# DROID.net
KiCad netlist of a schematic drawn in EAGLE
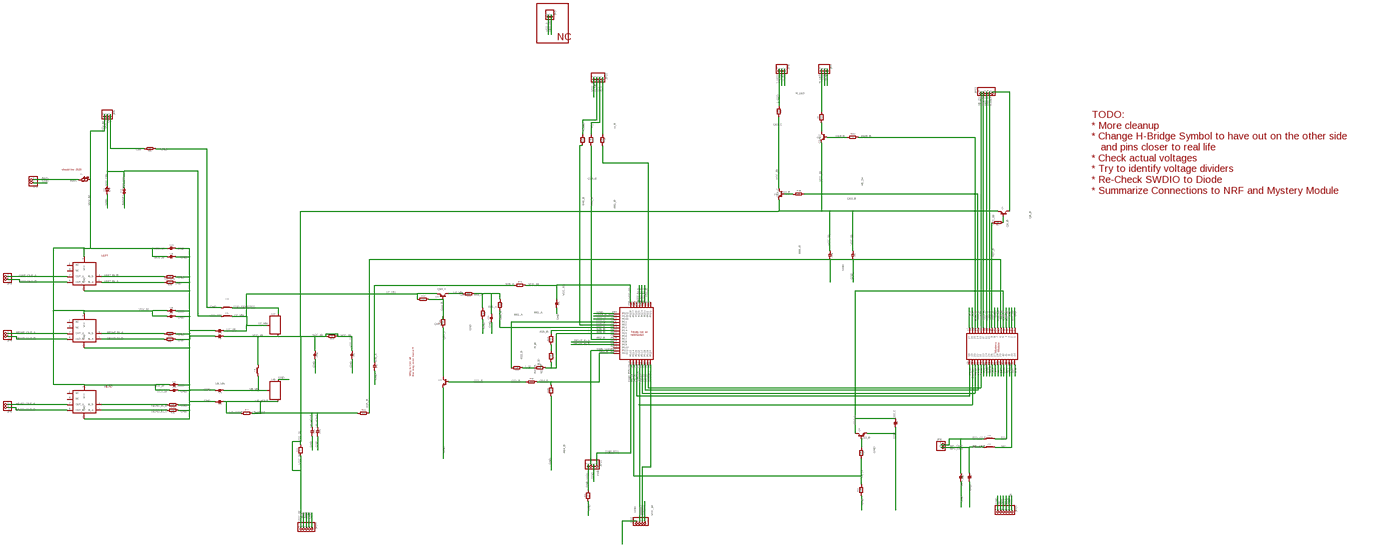
[diagram p0: schematic, sheet 1, overview]
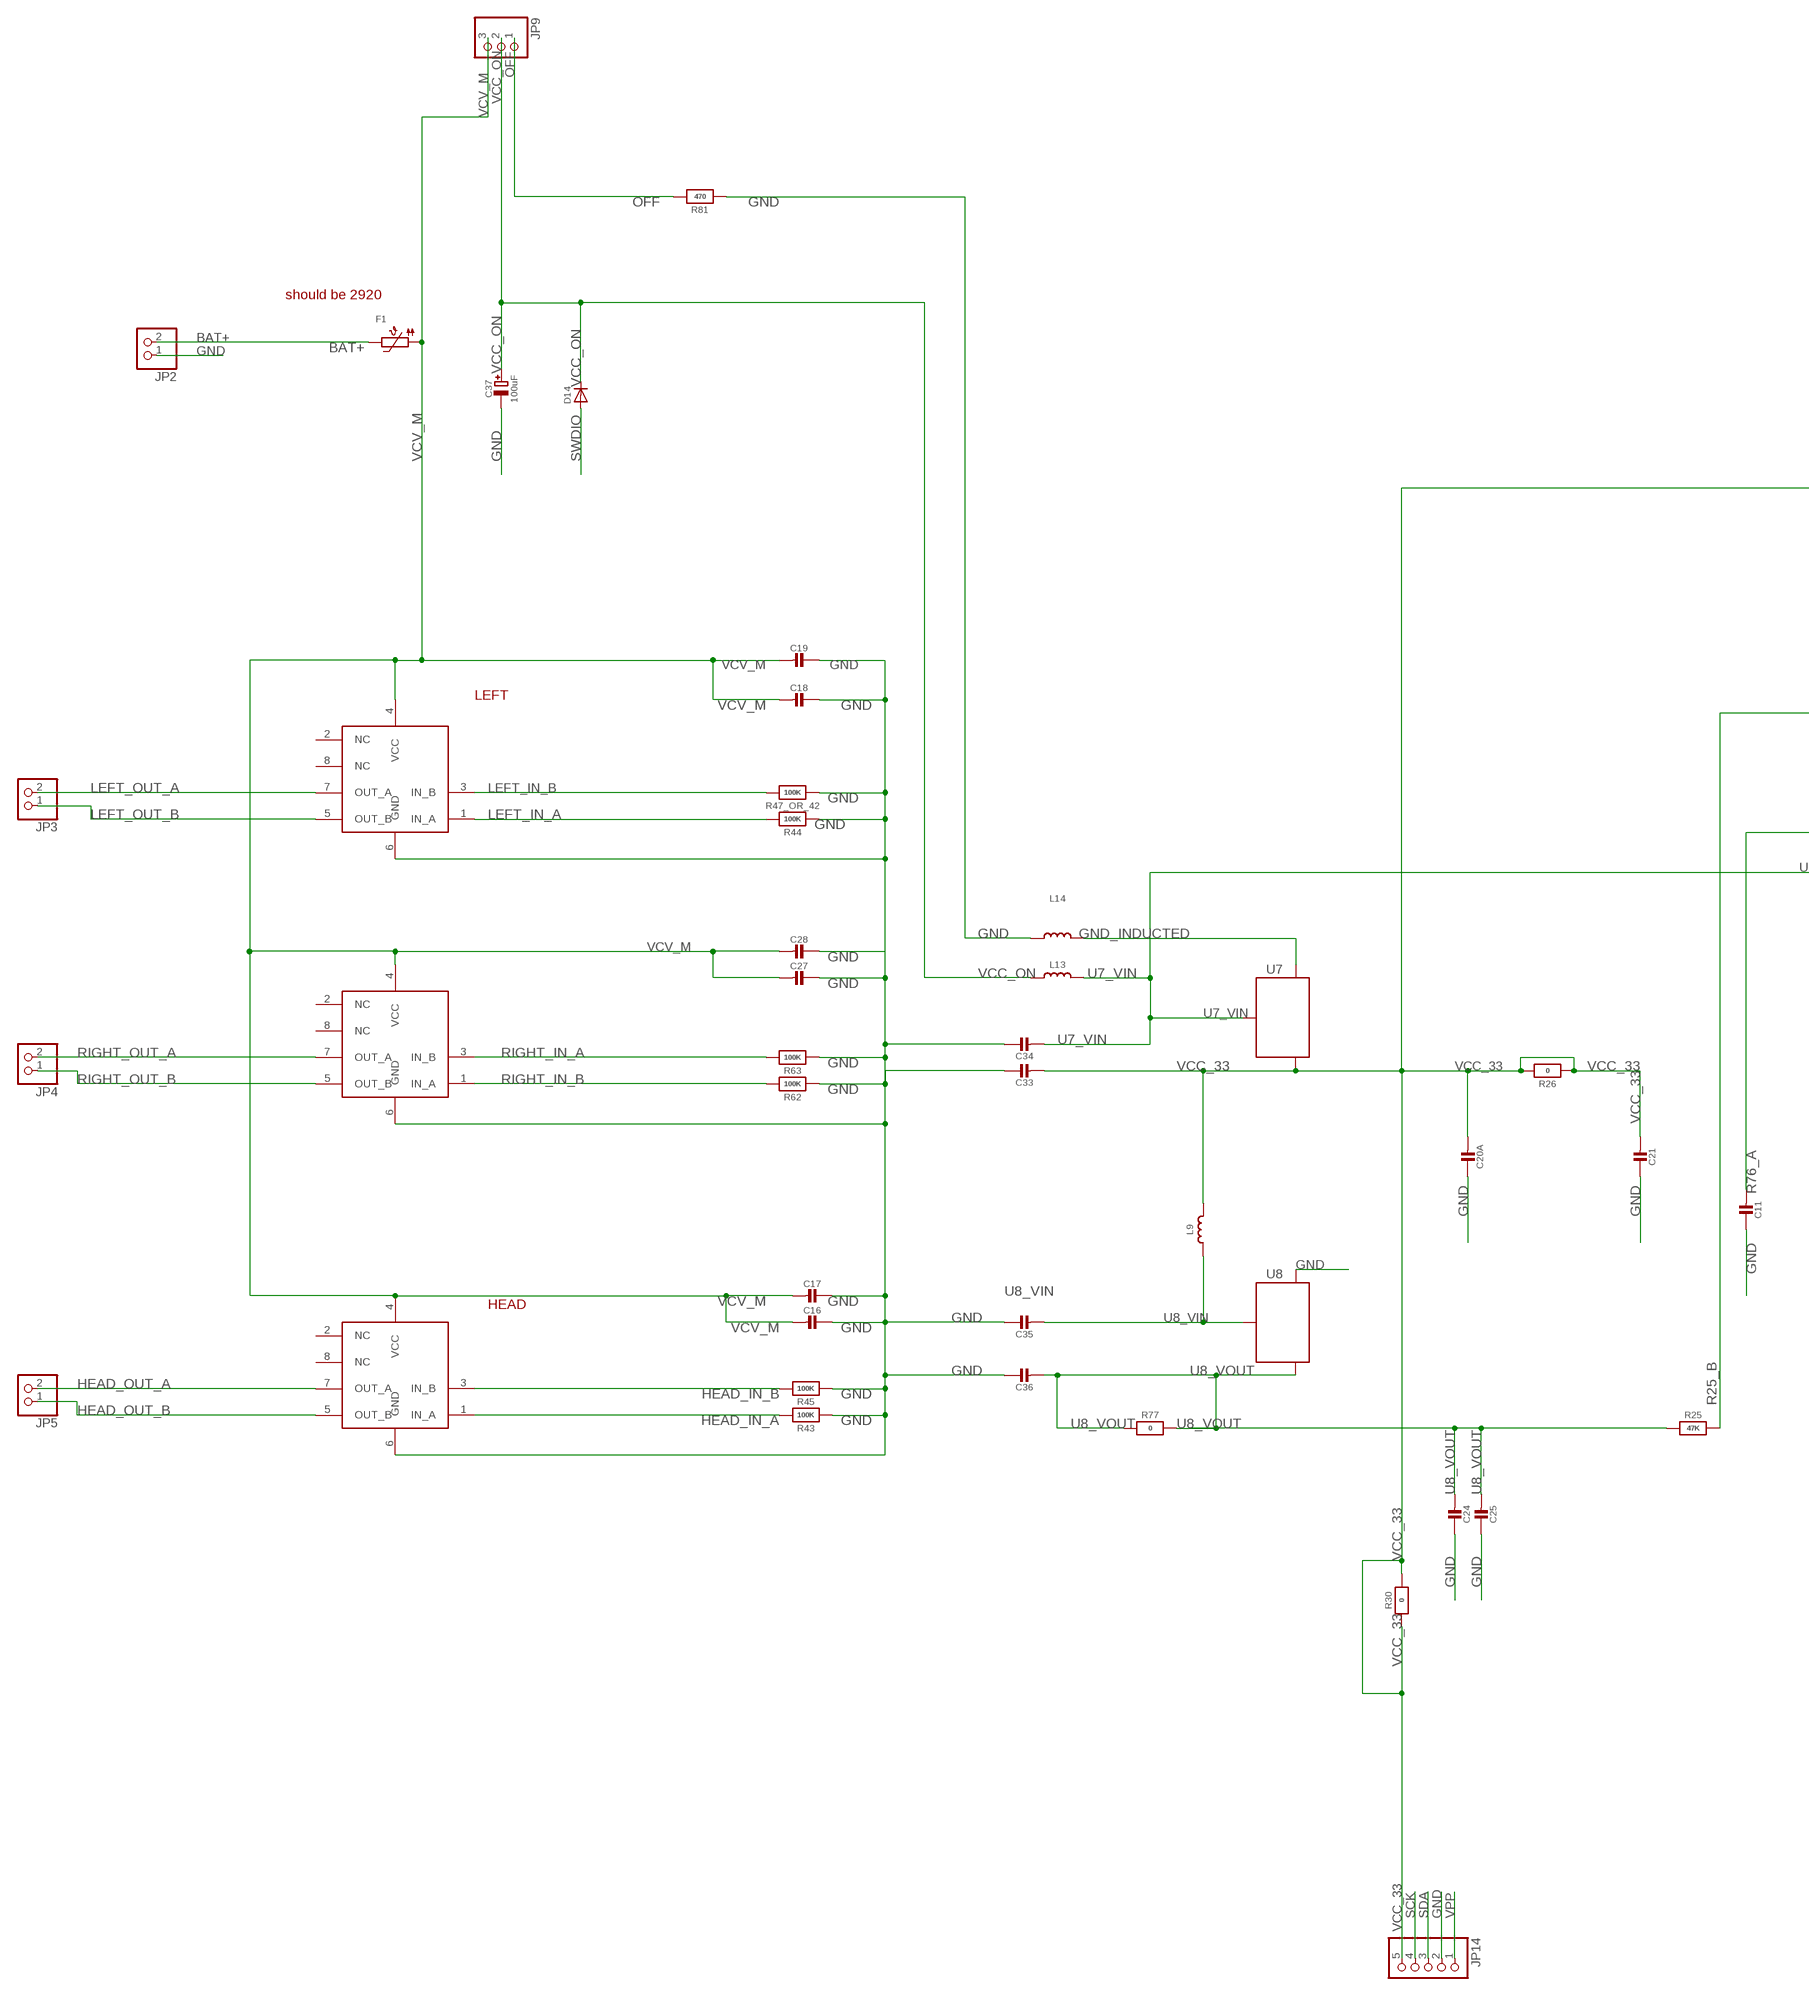
[diagram p1: schematic, sheet 1, part 1 of 5]
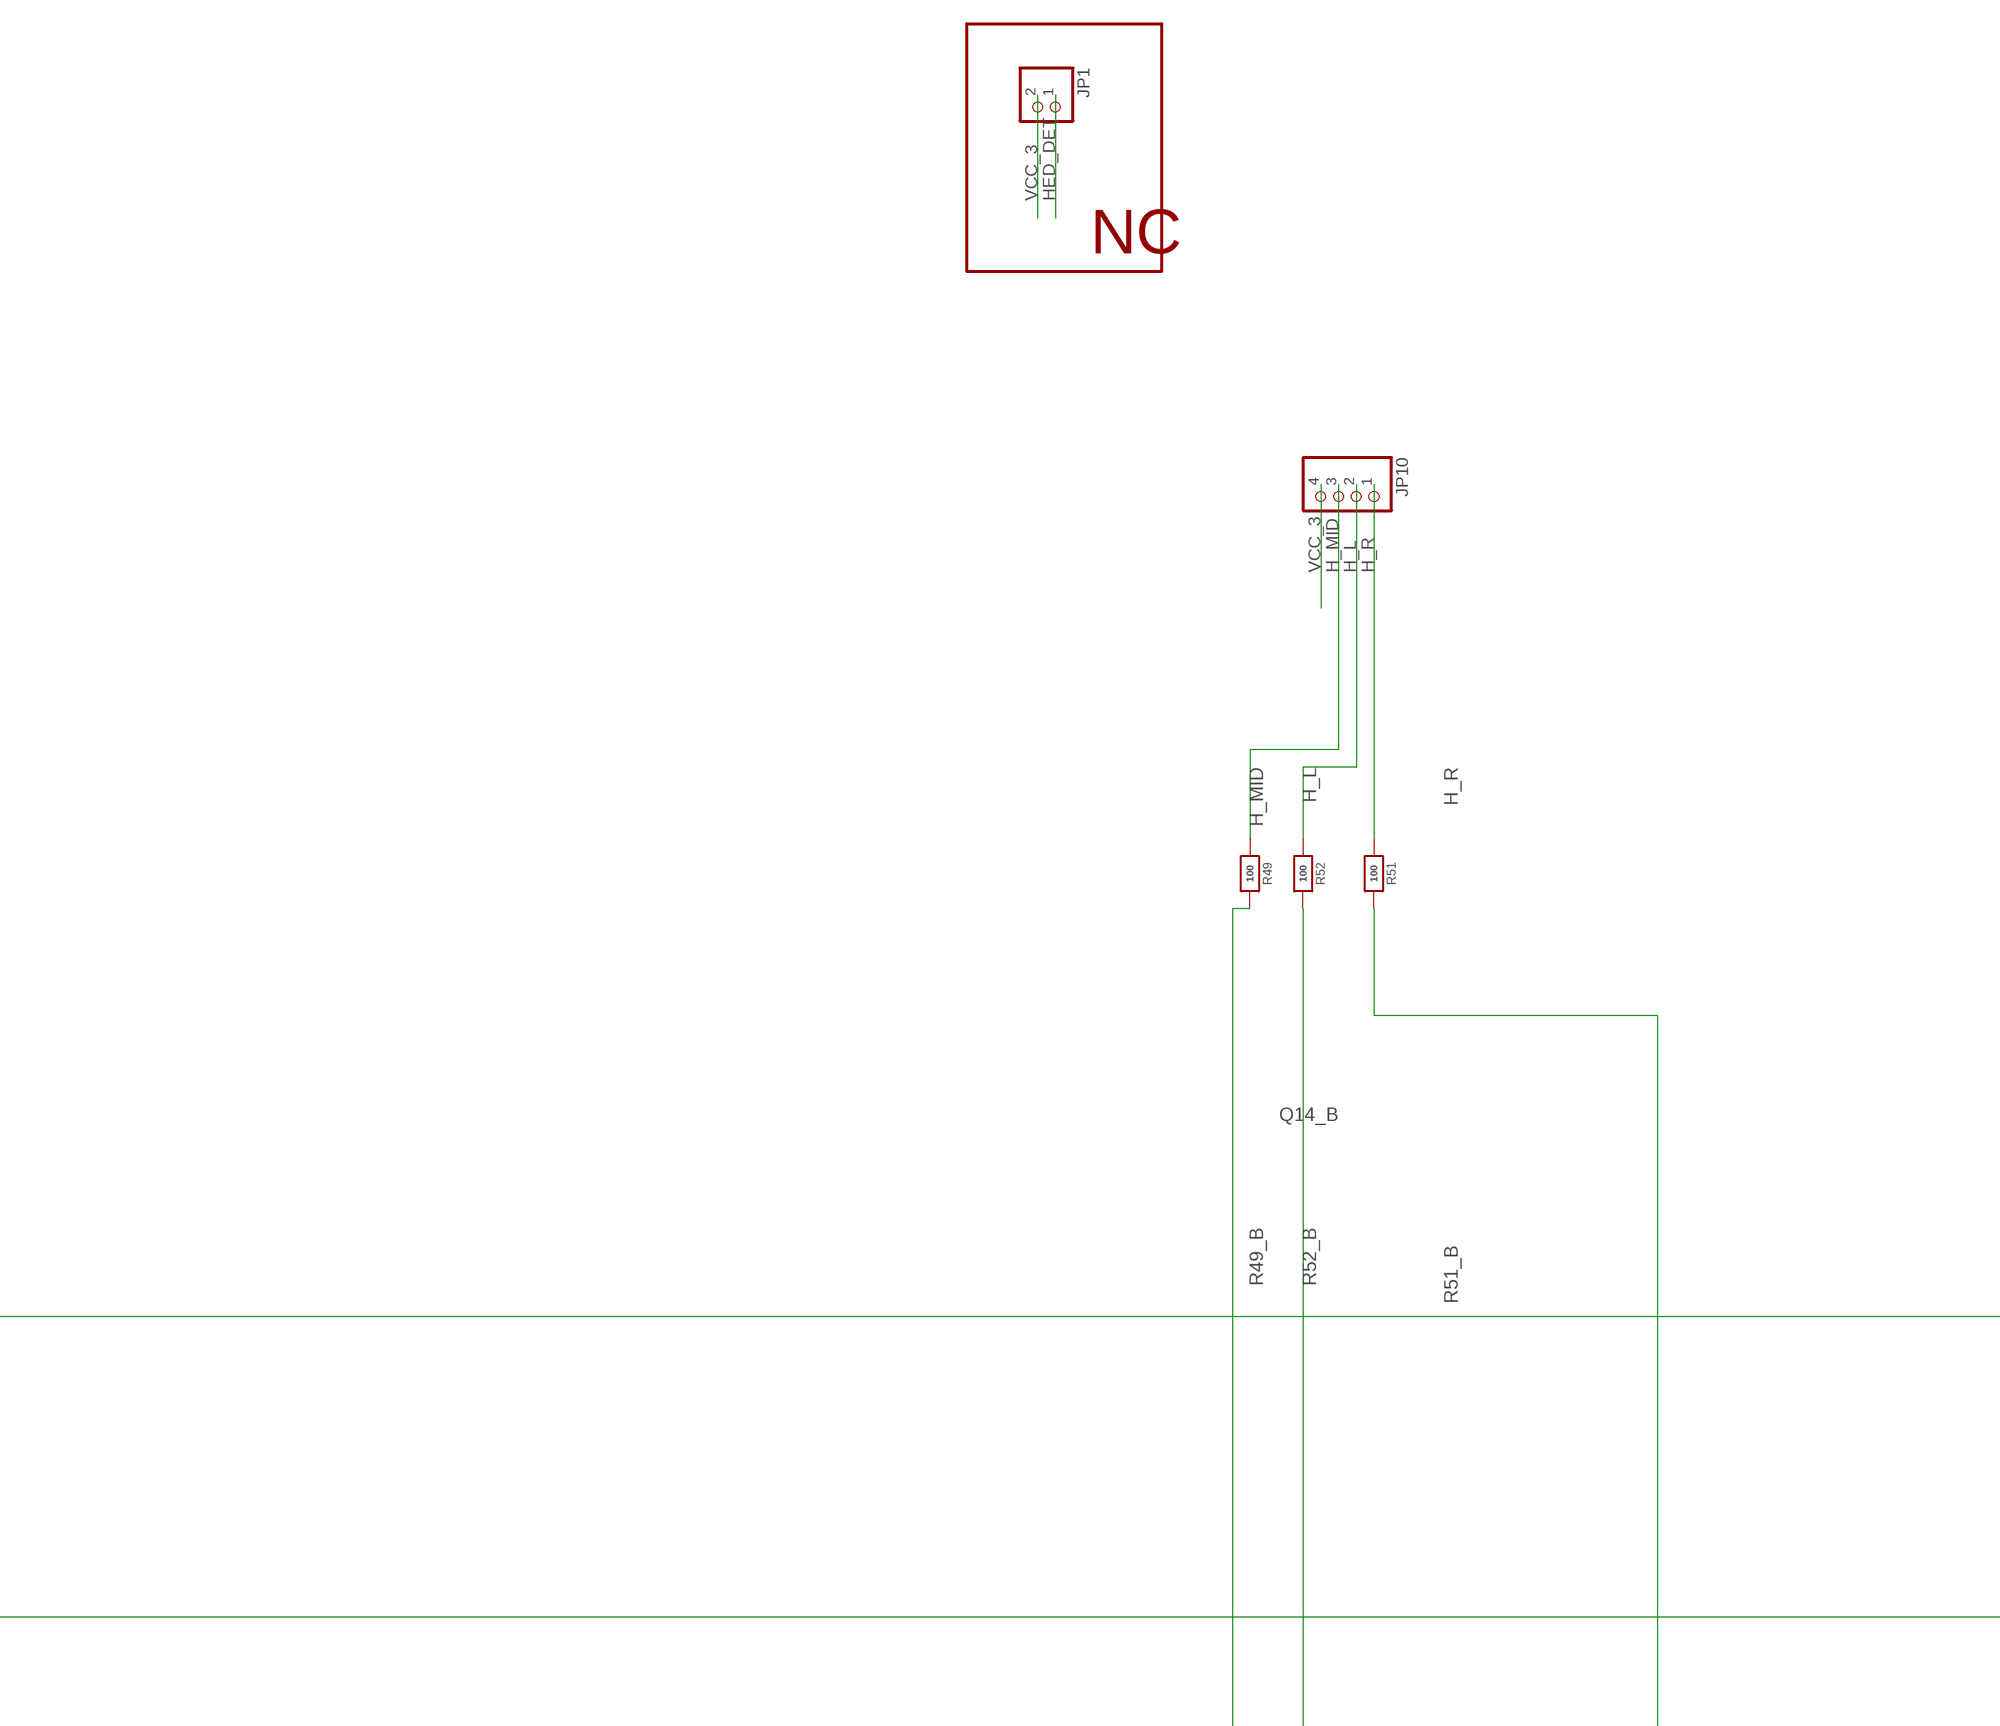
[diagram p2: schematic, sheet 1, part 2 of 5]
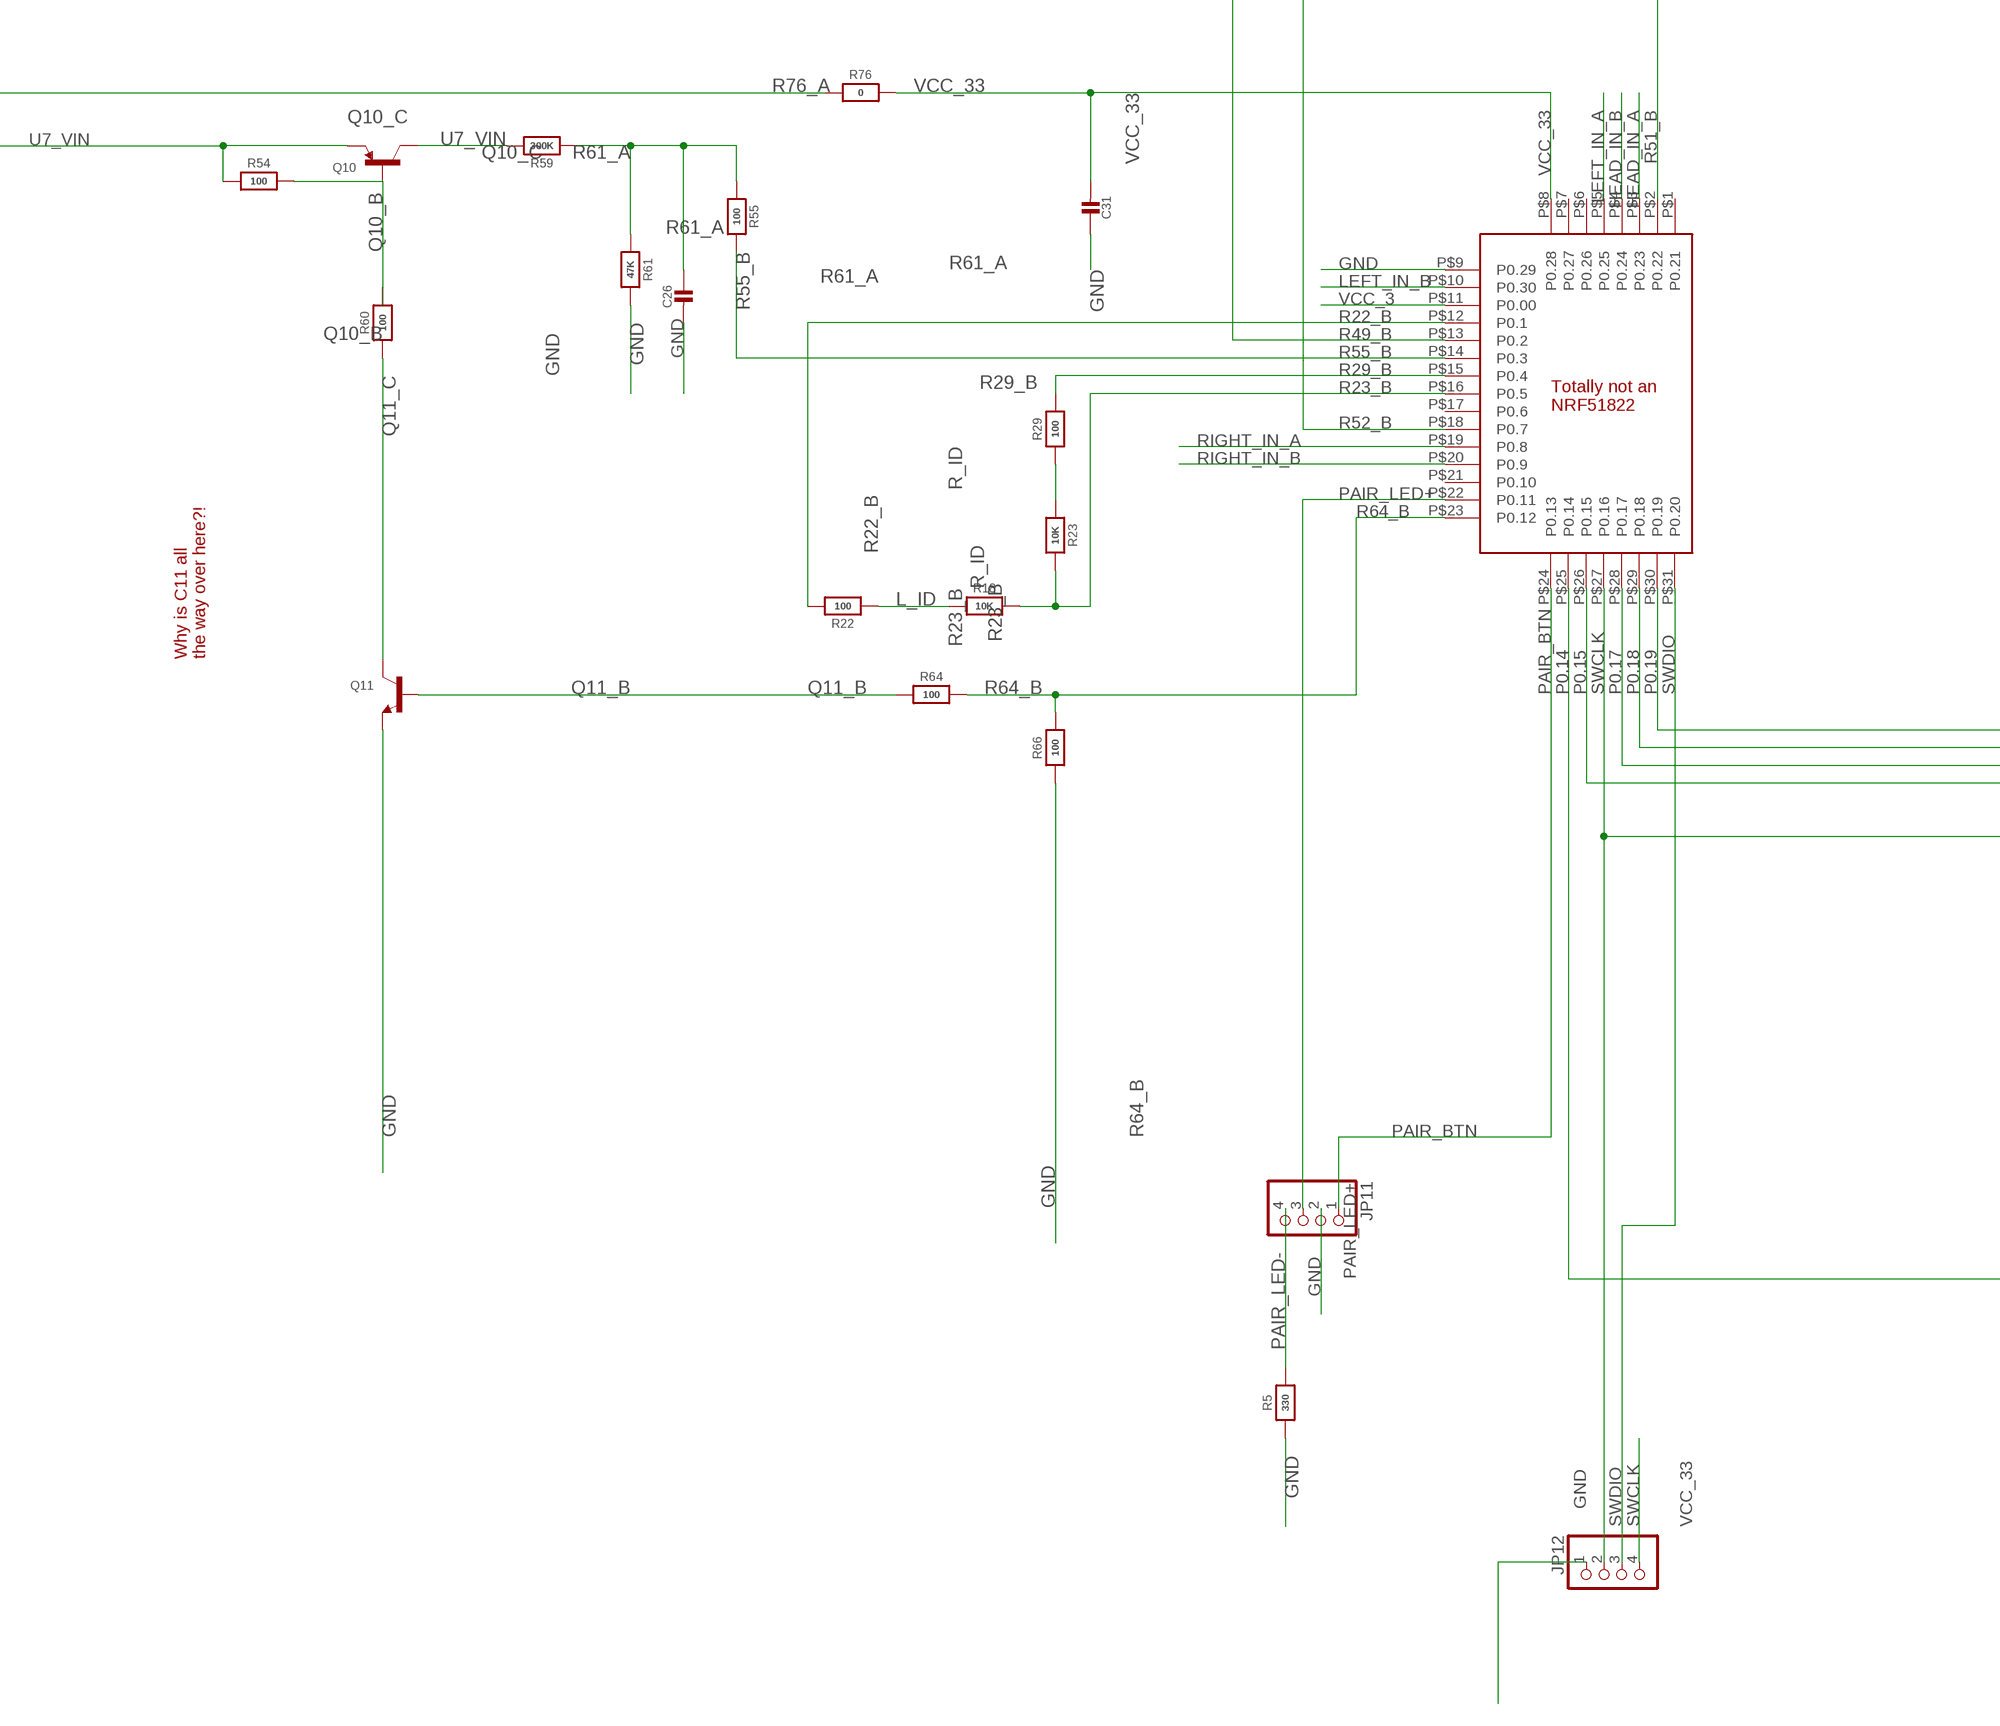
[diagram p3: schematic, sheet 1, part 3 of 5]
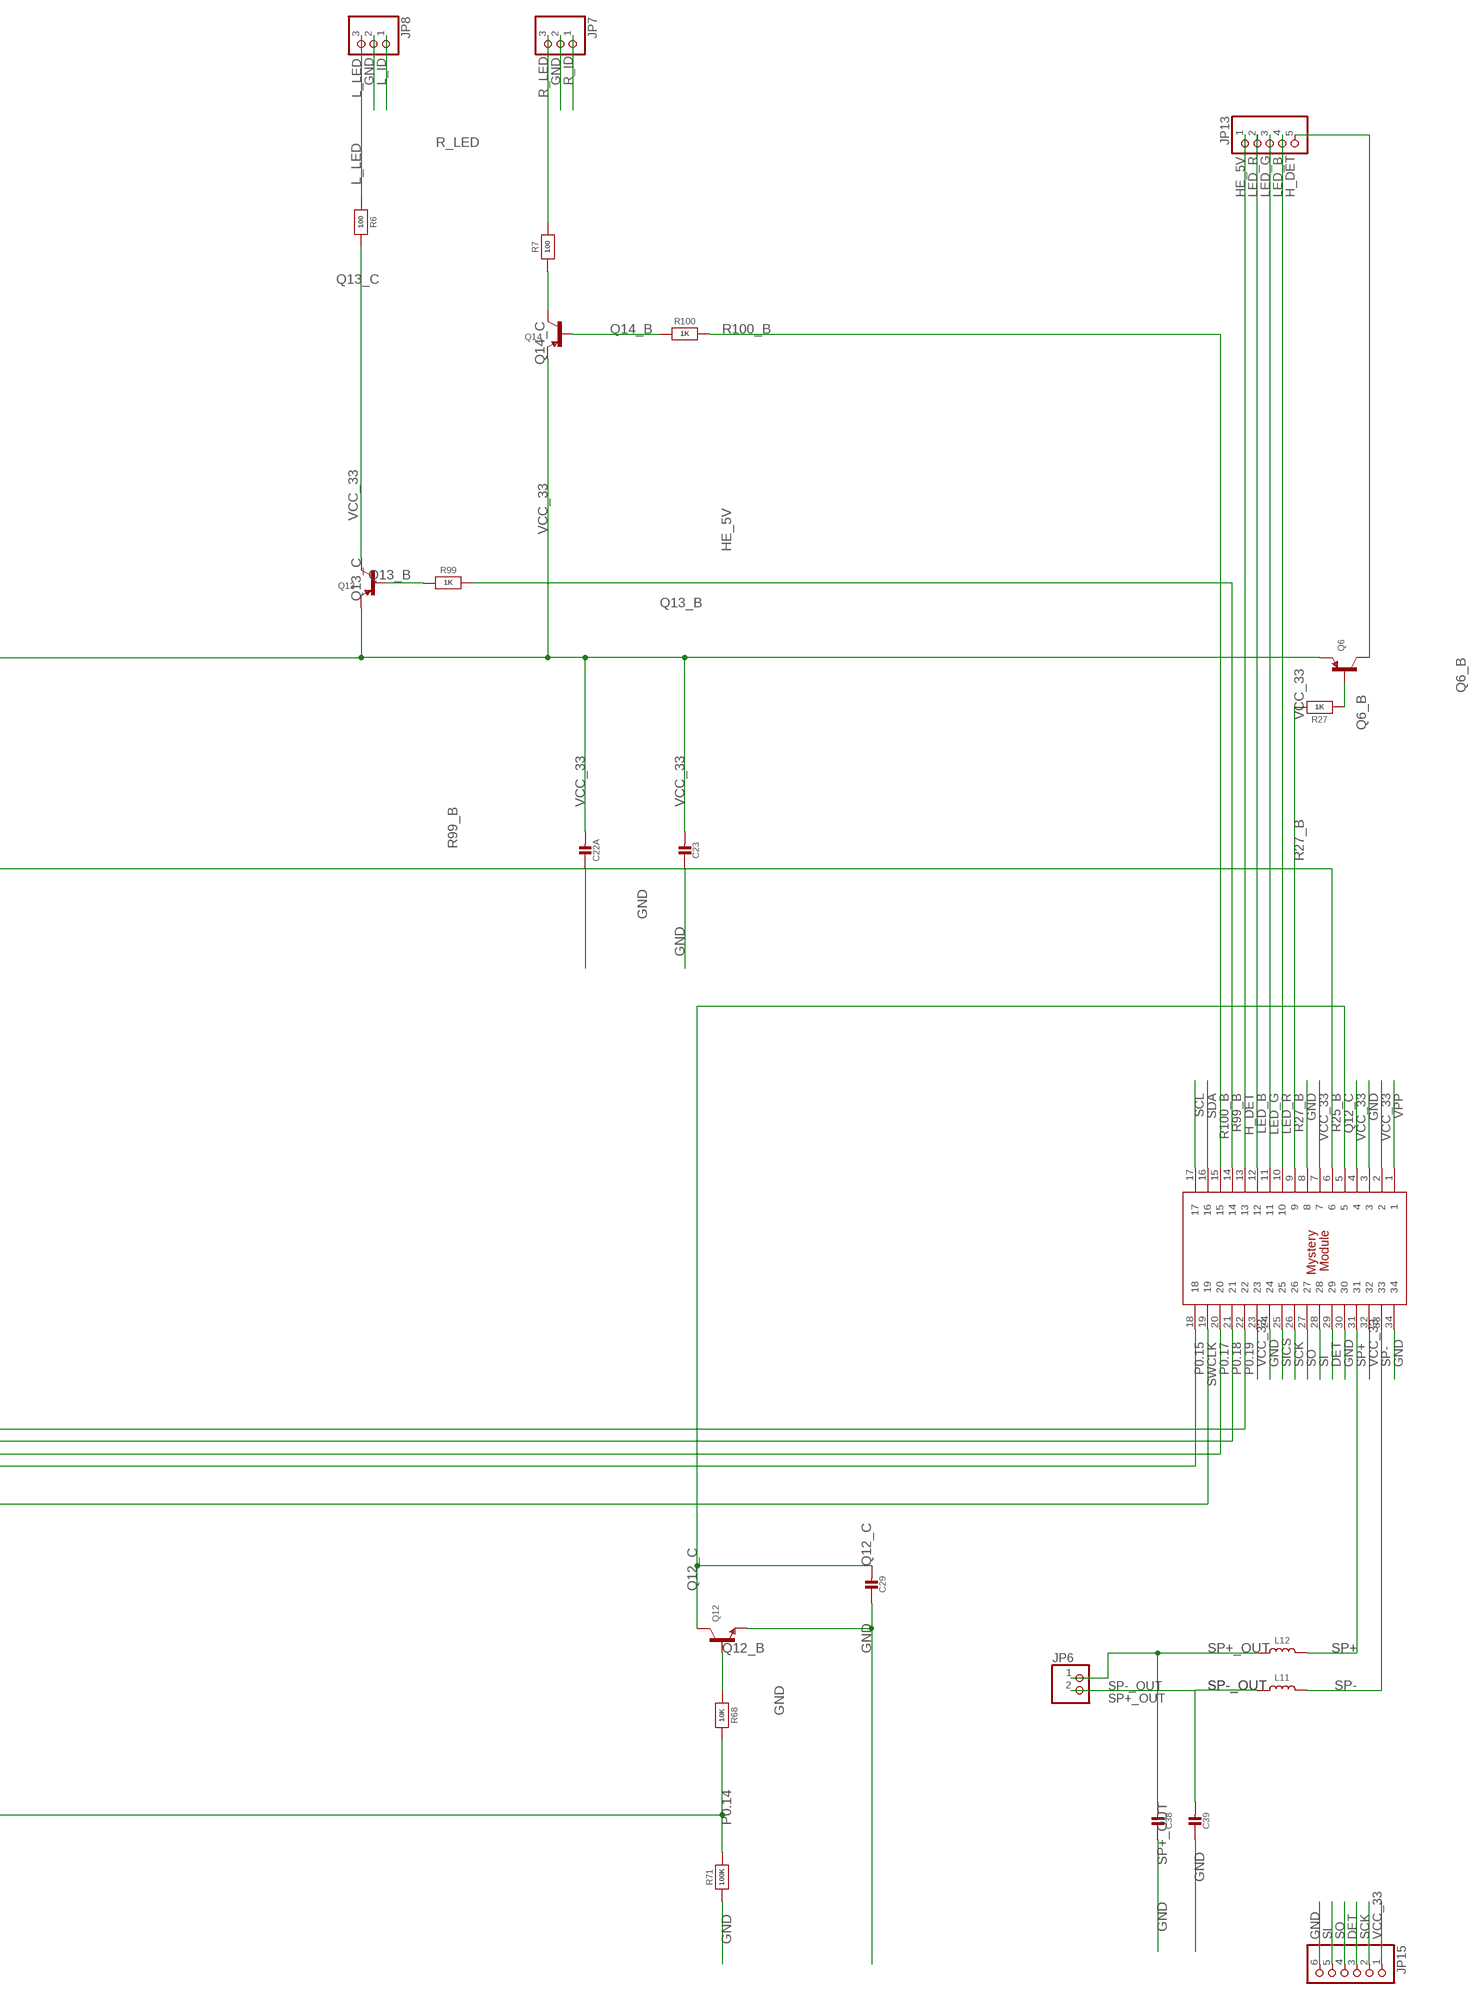
[diagram p4: schematic, sheet 1, part 4 of 5]
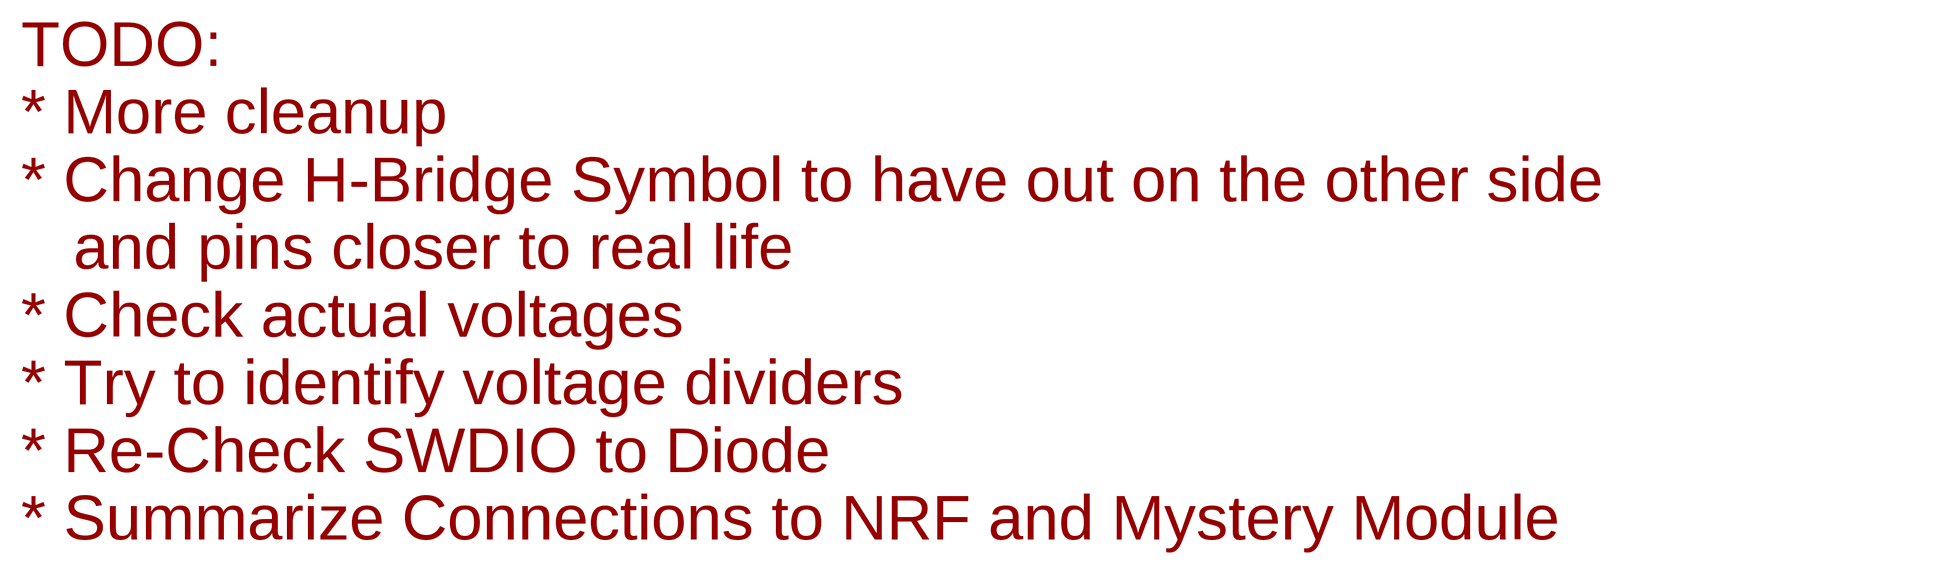
[diagram p5: schematic, sheet 1, part 5 of 5]

(export (version "E")
  (design (tool "Eeschema 10.0.6"))
  (components
    (comp (ref "C11")
      (value "CAP_CERAMIC0603_NO")
      (footprint "eagle-import:0603-NO")
      (libsource (lib "eagle-import") (part "CAP_CERAMIC0603_NO"))
    )
    (comp (ref "C16")
      (value "CAP_CERAMIC0603_NO")
      (footprint "eagle-import:0603-NO")
      (libsource (lib "eagle-import") (part "CAP_CERAMIC0603_NO"))
    )
    (comp (ref "C17")
      (value "CAP_CERAMIC_0805MP")
      (footprint "eagle-import:_0805MP")
      (libsource (lib "eagle-import") (part "CAP_CERAMIC_0805MP"))
    )
    (comp (ref "C18")
      (value "CAP_CERAMIC0603_NO")
      (footprint "eagle-import:0603-NO")
      (libsource (lib "eagle-import") (part "CAP_CERAMIC0603_NO"))
    )
    (comp (ref "C19")
      (value "CAP_CERAMIC_0805MP")
      (footprint "eagle-import:_0805MP")
      (libsource (lib "eagle-import") (part "CAP_CERAMIC_0805MP"))
    )
    (comp (ref "C20A")
      (value "CAP_CERAMIC_0805MP")
      (footprint "eagle-import:_0805MP")
      (libsource (lib "eagle-import") (part "CAP_CERAMIC_0805MP"))
    )
    (comp (ref "C21")
      (value "CAP_CERAMIC0603_NO")
      (footprint "eagle-import:0603-NO")
      (libsource (lib "eagle-import") (part "CAP_CERAMIC0603_NO"))
    )
    (comp (ref "C22A")
      (value "CAP_CERAMIC_0805MP")
      (footprint "eagle-import:_0805MP")
      (libsource (lib "eagle-import") (part "CAP_CERAMIC_0805MP"))
    )
    (comp (ref "C23")
      (value "CAP_CERAMIC0603_NO")
      (footprint "eagle-import:0603-NO")
      (libsource (lib "eagle-import") (part "CAP_CERAMIC0603_NO"))
    )
    (comp (ref "C24")
      (value "CAP_CERAMIC0603_NO")
      (footprint "eagle-import:0603-NO")
      (libsource (lib "eagle-import") (part "CAP_CERAMIC0603_NO"))
    )
    (comp (ref "C25")
      (value "CAP_CERAMIC0603_NO")
      (footprint "eagle-import:0603-NO")
      (libsource (lib "eagle-import") (part "CAP_CERAMIC0603_NO"))
    )
    (comp (ref "C26")
      (value "CAP_CERAMIC0603_NO")
      (footprint "eagle-import:0603-NO")
      (libsource (lib "eagle-import") (part "CAP_CERAMIC0603_NO"))
    )
    (comp (ref "C27")
      (value "CAP_CERAMIC0603_NO")
      (footprint "eagle-import:0603-NO")
      (libsource (lib "eagle-import") (part "CAP_CERAMIC0603_NO"))
    )
    (comp (ref "C28")
      (value "CAP_CERAMIC_0805MP")
      (footprint "eagle-import:_0805MP")
      (libsource (lib "eagle-import") (part "CAP_CERAMIC_0805MP"))
    )
    (comp (ref "C29")
      (value "CAP_CERAMIC0603_NO")
      (footprint "eagle-import:0603-NO")
      (libsource (lib "eagle-import") (part "CAP_CERAMIC0603_NO"))
    )
    (comp (ref "C31")
      (value "CAP_CERAMIC0603_NO")
      (footprint "eagle-import:0603-NO")
      (libsource (lib "eagle-import") (part "CAP_CERAMIC0603_NO"))
    )
    (comp (ref "C33")
      (value "CAP_CERAMIC0603_NO")
      (footprint "eagle-import:0603-NO")
      (libsource (lib "eagle-import") (part "CAP_CERAMIC0603_NO"))
    )
    (comp (ref "C34")
      (value "CAP_CERAMIC0603_NO")
      (footprint "eagle-import:0603-NO")
      (libsource (lib "eagle-import") (part "CAP_CERAMIC0603_NO"))
    )
    (comp (ref "C35")
      (value "CAP_CERAMIC0603_NO")
      (footprint "eagle-import:0603-NO")
      (libsource (lib "eagle-import") (part "CAP_CERAMIC0603_NO"))
    )
    (comp (ref "C36")
      (value "CAP_CERAMIC0603_NO")
      (footprint "eagle-import:0603-NO")
      (libsource (lib "eagle-import") (part "CAP_CERAMIC0603_NO"))
    )
    (comp (ref "C37")
      (value "100uF")
      (footprint "eagle-import:PANASONIC_D")
      (libsource (lib "eagle-import") (part "CAP_ELECTROLYTICPANASONIC_D"))
    )
    (comp (ref "C38")
      (value "CAP_CERAMIC0603_NO")
      (footprint "eagle-import:0603-NO")
      (libsource (lib "eagle-import") (part "CAP_CERAMIC0603_NO"))
    )
    (comp (ref "C39")
      (value "CAP_CERAMIC0603_NO")
      (footprint "eagle-import:0603-NO")
      (libsource (lib "eagle-import") (part "CAP_CERAMIC0603_NO"))
    )
    (comp (ref "D14")
      (value "DIODESOD-323")
      (footprint "eagle-import:SOD-323")
      (libsource (lib "eagle-import") (part "DIODESOD-323"))
    )
    (comp (ref "F1")
      (value "PTC1812")
      (footprint "eagle-import:PTC1812")
      (libsource (lib "eagle-import") (part "PTC1812"))
    )
    (comp (ref "JP1")
      (value "HEADER-1X2ROUND")
      (footprint "eagle-import:1X02_ROUND")
      (libsource (lib "eagle-import") (part "HEADER-1X2ROUND"))
    )
    (comp (ref "JP2")
      (value "HEADER-1X2ROUND")
      (footprint "eagle-import:1X02_ROUND")
      (libsource (lib "eagle-import") (part "HEADER-1X2ROUND"))
    )
    (comp (ref "JP3")
      (value "HEADER-1X2ROUND")
      (footprint "eagle-import:1X02_ROUND")
      (libsource (lib "eagle-import") (part "HEADER-1X2ROUND"))
    )
    (comp (ref "JP4")
      (value "HEADER-1X2ROUND")
      (footprint "eagle-import:1X02_ROUND")
      (libsource (lib "eagle-import") (part "HEADER-1X2ROUND"))
    )
    (comp (ref "JP5")
      (value "HEADER-1X2ROUND")
      (footprint "eagle-import:1X02_ROUND")
      (libsource (lib "eagle-import") (part "HEADER-1X2ROUND"))
    )
    (comp (ref "JP6")
      (value "HEADER-1X2ROUND")
      (footprint "eagle-import:1X02_ROUND")
      (libsource (lib "eagle-import") (part "HEADER-1X2ROUND"))
    )
    (comp (ref "JP7")
      (value "HEADER-1X3ROUND")
      (footprint "eagle-import:1X03_ROUND")
      (libsource (lib "eagle-import") (part "HEADER-1X3ROUND"))
    )
    (comp (ref "JP8")
      (value "HEADER-1X3ROUND")
      (footprint "eagle-import:1X03_ROUND")
      (libsource (lib "eagle-import") (part "HEADER-1X3ROUND"))
    )
    (comp (ref "JP9")
      (value "HEADER-1X3ROUND")
      (footprint "eagle-import:1X03_ROUND")
      (libsource (lib "eagle-import") (part "HEADER-1X3ROUND"))
    )
    (comp (ref "JP10")
      (value "HEADER-1X4ROUND")
      (footprint "eagle-import:1X04_ROUND")
      (libsource (lib "eagle-import") (part "HEADER-1X4ROUND"))
    )
    (comp (ref "JP11")
      (value "HEADER-1X4ROUND")
      (footprint "eagle-import:1X04_ROUND")
      (libsource (lib "eagle-import") (part "HEADER-1X4ROUND"))
    )
    (comp (ref "JP12")
      (value "HEADER-1X4ROUND")
      (footprint "eagle-import:1X04_ROUND")
      (libsource (lib "eagle-import") (part "HEADER-1X4ROUND"))
    )
    (comp (ref "JP13")
      (value "HEADER-1X5ROUND")
      (footprint "eagle-import:1X05_ROUND")
      (libsource (lib "eagle-import") (part "HEADER-1X5ROUND"))
    )
    (comp (ref "JP14")
      (value "HEADER-1X5ROUND")
      (footprint "eagle-import:1X05_ROUND")
      (libsource (lib "eagle-import") (part "HEADER-1X5ROUND"))
    )
    (comp (ref "JP15")
      (value "HEADER-1X6ROUND")
      (footprint "eagle-import:1X06_ROUND")
      (libsource (lib "eagle-import") (part "HEADER-1X6ROUND"))
    )
    (comp (ref "L9")
      (value "INDUCTOR0805-NO")
      (footprint "eagle-import:0805-NO")
      (libsource (lib "eagle-import") (part "INDUCTOR0805-NO"))
    )
    (comp (ref "L11")
      (value "INDUCTOR0603_NO")
      (footprint "eagle-import:0603-NO")
      (libsource (lib "eagle-import") (part "INDUCTOR0603_NO"))
    )
    (comp (ref "L12")
      (value "INDUCTOR0603_NO")
      (footprint "eagle-import:0603-NO")
      (libsource (lib "eagle-import") (part "INDUCTOR0603_NO"))
    )
    (comp (ref "L13")
      (value "INDUCTOR0805-NO")
      (footprint "eagle-import:0805-NO")
      (libsource (lib "eagle-import") (part "INDUCTOR0805-NO"))
    )
    (comp (ref "L14")
      (value "INDUCTOR0805-NO")
      (footprint "eagle-import:0805-NO")
      (libsource (lib "eagle-import") (part "INDUCTOR0805-NO"))
    )
    (comp (ref "Q6")
      (value "TRANSISTOR_PNPSOT23-REFLOW")
      (footprint "eagle-import:SOT23-R")
      (libsource (lib "eagle-import") (part "TRANSISTOR_PNPSOT23-REFLOW"))
    )
    (comp (ref "Q10")
      (value "TRANSISTOR_PNPSOT23-REFLOW")
      (footprint "eagle-import:SOT23-R")
      (libsource (lib "eagle-import") (part "TRANSISTOR_PNPSOT23-REFLOW"))
    )
    (comp (ref "Q11")
      (value "TRANSISTOR_NPNWIDE")
      (footprint "eagle-import:SOT23-WIDE")
      (libsource (lib "eagle-import") (part "TRANSISTOR_NPNWIDE"))
    )
    (comp (ref "Q12")
      (value "TRANSISTOR_NPNWIDE")
      (footprint "eagle-import:SOT23-WIDE")
      (libsource (lib "eagle-import") (part "TRANSISTOR_NPNWIDE"))
    )
    (comp (ref "Q13")
      (value "TRANSISTOR_PNPSOT23-REFLOW")
      (footprint "eagle-import:SOT23-R")
      (libsource (lib "eagle-import") (part "TRANSISTOR_PNPSOT23-REFLOW"))
    )
    (comp (ref "Q14")
      (value "TRANSISTOR_PNPSOT23-REFLOW")
      (footprint "eagle-import:SOT23-R")
      (libsource (lib "eagle-import") (part "TRANSISTOR_PNPSOT23-REFLOW"))
    )
    (comp (ref "R5")
      (value "330")
      (footprint "eagle-import:0603-NO")
      (libsource (lib "eagle-import") (part "RESISTOR_0603_NOOUT"))
    )
    (comp (ref "R6")
      (value "100")
      (footprint "eagle-import:0603-NO")
      (libsource (lib "eagle-import") (part "RESISTOR_0603_NOOUT"))
    )
    (comp (ref "R7")
      (value "100")
      (footprint "eagle-import:0603-NO")
      (libsource (lib "eagle-import") (part "RESISTOR_0603_NOOUT"))
    )
    (comp (ref "R18")
      (value "10K")
      (footprint "eagle-import:0603-NO")
      (libsource (lib "eagle-import") (part "RESISTOR_0603_NOOUT"))
    )
    (comp (ref "R22")
      (value "100")
      (footprint "eagle-import:0603-NO")
      (libsource (lib "eagle-import") (part "RESISTOR_0603_NOOUT"))
    )
    (comp (ref "R23")
      (value "10K")
      (footprint "eagle-import:0603-NO")
      (libsource (lib "eagle-import") (part "RESISTOR_0603_NOOUT"))
    )
    (comp (ref "R25")
      (value "47K")
      (footprint "eagle-import:0603-NO")
      (libsource (lib "eagle-import") (part "RESISTOR_0603_NOOUT"))
    )
    (comp (ref "R26")
      (value "0")
      (footprint "eagle-import:0603-NO")
      (libsource (lib "eagle-import") (part "RESISTOR_0603_NOOUT"))
    )
    (comp (ref "R27")
      (value "1K")
      (footprint "eagle-import:0603-NO")
      (libsource (lib "eagle-import") (part "RESISTOR_0603_NOOUT"))
    )
    (comp (ref "R29")
      (value "100")
      (footprint "eagle-import:0603-NO")
      (libsource (lib "eagle-import") (part "RESISTOR_0603_NOOUT"))
    )
    (comp (ref "R30")
      (value "0")
      (footprint "eagle-import:0603-NO")
      (libsource (lib "eagle-import") (part "RESISTOR_0603_NOOUT"))
    )
    (comp (ref "R43")
      (value "100K")
      (footprint "eagle-import:0603-NO")
      (libsource (lib "eagle-import") (part "RESISTOR_0603_NOOUT"))
    )
    (comp (ref "R44")
      (value "100K")
      (footprint "eagle-import:0603-NO")
      (libsource (lib "eagle-import") (part "RESISTOR_0603_NOOUT"))
    )
    (comp (ref "R45")
      (value "100K")
      (footprint "eagle-import:0603-NO")
      (libsource (lib "eagle-import") (part "RESISTOR_0603_NOOUT"))
    )
    (comp (ref "R47_OR_42")
      (value "100K")
      (footprint "eagle-import:0603-NO")
      (libsource (lib "eagle-import") (part "RESISTOR_0603_NOOUT"))
    )
    (comp (ref "R49")
      (value "100")
      (footprint "eagle-import:0603-NO")
      (libsource (lib "eagle-import") (part "RESISTOR_0603_NOOUT"))
    )
    (comp (ref "R51")
      (value "100")
      (footprint "eagle-import:0603-NO")
      (libsource (lib "eagle-import") (part "RESISTOR_0603_NOOUT"))
    )
    (comp (ref "R52")
      (value "100")
      (footprint "eagle-import:0603-NO")
      (libsource (lib "eagle-import") (part "RESISTOR_0603_NOOUT"))
    )
    (comp (ref "R54")
      (value "100")
      (footprint "eagle-import:0603-NO")
      (libsource (lib "eagle-import") (part "RESISTOR_0603_NOOUT"))
    )
    (comp (ref "R55")
      (value "100")
      (footprint "eagle-import:0603-NO")
      (libsource (lib "eagle-import") (part "RESISTOR_0603_NOOUT"))
    )
    (comp (ref "R59")
      (value "300K")
      (footprint "eagle-import:0603-NO")
      (libsource (lib "eagle-import") (part "RESISTOR_0603_NOOUT"))
    )
    (comp (ref "R60")
      (value "100")
      (footprint "eagle-import:0603-NO")
      (libsource (lib "eagle-import") (part "RESISTOR_0603_NOOUT"))
    )
    (comp (ref "R61")
      (value "47K")
      (footprint "eagle-import:0603-NO")
      (libsource (lib "eagle-import") (part "RESISTOR_0603_NOOUT"))
    )
    (comp (ref "R62")
      (value "100K")
      (footprint "eagle-import:0603-NO")
      (libsource (lib "eagle-import") (part "RESISTOR_0603_NOOUT"))
    )
    (comp (ref "R63")
      (value "100K")
      (footprint "eagle-import:0603-NO")
      (libsource (lib "eagle-import") (part "RESISTOR_0603_NOOUT"))
    )
    (comp (ref "R64")
      (value "100")
      (footprint "eagle-import:0603-NO")
      (libsource (lib "eagle-import") (part "RESISTOR_0603_NOOUT"))
    )
    (comp (ref "R66")
      (value "100")
      (footprint "eagle-import:0603-NO")
      (libsource (lib "eagle-import") (part "RESISTOR_0603_NOOUT"))
    )
    (comp (ref "R68")
      (value "10K")
      (footprint "eagle-import:0603-NO")
      (libsource (lib "eagle-import") (part "RESISTOR_0603_NOOUT"))
    )
    (comp (ref "R71")
      (value "100K")
      (footprint "eagle-import:0603-NO")
      (libsource (lib "eagle-import") (part "RESISTOR_0603_NOOUT"))
    )
    (comp (ref "R76")
      (value "0")
      (footprint "eagle-import:0603-NO")
      (libsource (lib "eagle-import") (part "RESISTOR_0603_NOOUT"))
    )
    (comp (ref "R77")
      (value "0")
      (footprint "eagle-import:0603-NO")
      (libsource (lib "eagle-import") (part "RESISTOR_0603_NOOUT"))
    )
    (comp (ref "R81")
      (value "470")
      (footprint "eagle-import:_0805MP")
      (libsource (lib "eagle-import") (part "RESISTOR_0805MP"))
    )
    (comp (ref "R99")
      (value "1K")
      (footprint "eagle-import:0603-NO")
      (libsource (lib "eagle-import") (part "RESISTOR_0603_NOOUT"))
    )
    (comp (ref "R100")
      (value "1K")
      (footprint "eagle-import:0603-NO")
      (libsource (lib "eagle-import") (part "RESISTOR_0603_NOOUT"))
    )
    (comp (ref "U$1")
      (value "AM1037A")
      (footprint "eagle-import:SOIC8_208MIL")
      (libsource (lib "eagle-import") (part "AM1037A"))
    )
    (comp (ref "U$2")
      (value "AM1037A")
      (footprint "eagle-import:SOIC8_208MIL")
      (libsource (lib "eagle-import") (part "AM1037A"))
    )
    (comp (ref "U$3")
      (value "AM1037A")
      (footprint "eagle-import:SOIC8_208MIL")
      (libsource (lib "eagle-import") (part "AM1037A"))
    )
    (comp (ref "U$4")
      (value "KNRF51822_A24")
      (footprint "eagle-import:KNRF51822")
      (libsource (lib "eagle-import") (part "KNRF51822_A24"))
    )
    (comp (ref "U$5")
      (value "GPCD9TP340A_DROID")
      (footprint "eagle-import:GPCD9TP340A")
      (libsource (lib "eagle-import") (part "GPCD9TP340A_DROID"))
    )
    (comp (ref "U7")
      (value "ME62XX")
      (footprint "eagle-import:SOT89")
      (fields (field (name "MPN") "2DB1713-13"))
      (libsource (lib "eagle-import") (part "ME62XX"))
    )
    (comp (ref "U8")
      (value "ME62XX")
      (footprint "eagle-import:SOT89")
      (fields (field (name "MPN") "2DB1713-13"))
      (libsource (lib "eagle-import") (part "ME62XX"))
    )
  )
  (nets
    (net (code "1") (name "/BAT+") (class "Default")
      (node (ref "F1") (pin "P$2") (pinfunction "2_P$2") (pintype "passive"))
      (node (ref "JP2") (pin "2") (pinfunction "2_2") (pintype "passive"))
    )
    (net (code "2") (name "/DET") (class "Default")
      (node (ref "JP15") (pin "3") (pinfunction "3_3") (pintype "passive"))
      (node (ref "U$5") (pin "29") (pinfunction "29_29") (pintype "bidirectional"))
    )
    (net (code "3") (name "/GND") (class "Default")
      (node (ref "C11") (pin "1") (pinfunction "1_1") (pintype "passive"))
      (node (ref "C16") (pin "1") (pinfunction "1_1") (pintype "passive"))
      (node (ref "C17") (pin "1") (pinfunction "1_1") (pintype "passive"))
      (node (ref "C18") (pin "1") (pinfunction "1_1") (pintype "passive"))
      (node (ref "C19") (pin "1") (pinfunction "1_1") (pintype "passive"))
      (node (ref "C20A") (pin "1") (pinfunction "1_1") (pintype "passive"))
      (node (ref "C21") (pin "1") (pinfunction "1_1") (pintype "passive"))
      (node (ref "C22A") (pin "1") (pinfunction "1_1") (pintype "passive"))
      (node (ref "C23") (pin "1") (pinfunction "1_1") (pintype "passive"))
      (node (ref "C24") (pin "1") (pinfunction "1_1") (pintype "passive"))
      (node (ref "C25") (pin "1") (pinfunction "1_1") (pintype "passive"))
      (node (ref "C26") (pin "2") (pinfunction "2_2") (pintype "passive"))
      (node (ref "C27") (pin "1") (pinfunction "1_1") (pintype "passive"))
      (node (ref "C28") (pin "1") (pinfunction "1_1") (pintype "passive"))
      (node (ref "C29") (pin "1") (pinfunction "1_1") (pintype "passive"))
      (node (ref "C31") (pin "1") (pinfunction "1_1") (pintype "passive"))
      (node (ref "C33") (pin "1") (pinfunction "1_1") (pintype "passive"))
      (node (ref "C34") (pin "1") (pinfunction "1_1") (pintype "passive"))
      (node (ref "C35") (pin "1") (pinfunction "1_1") (pintype "passive"))
      (node (ref "C36") (pin "1") (pinfunction "1_1") (pintype "passive"))
      (node (ref "C37") (pin "-") (pinfunction "-_-") (pintype "passive"))
      (node (ref "C38") (pin "1") (pinfunction "1_1") (pintype "passive"))
      (node (ref "C39") (pin "1") (pinfunction "1_1") (pintype "passive"))
      (node (ref "JP11") (pin "2") (pinfunction "2_2") (pintype "passive"))
      (node (ref "JP12") (pin "1") (pinfunction "1_1") (pintype "passive"))
      (node (ref "JP14") (pin "2") (pinfunction "2_2") (pintype "passive"))
      (node (ref "JP15") (pin "6") (pinfunction "6_6") (pintype "passive"))
      (node (ref "JP2") (pin "1") (pinfunction "1_1") (pintype "passive"))
      (node (ref "JP7") (pin "2") (pinfunction "2_2") (pintype "passive"))
      (node (ref "JP8") (pin "2") (pinfunction "2_2") (pintype "passive"))
      (node (ref "L14") (pin "1") (pinfunction "1_1") (pintype "passive"))
      (node (ref "Q11") (pin "2") (pinfunction "E_2") (pintype "passive"))
      (node (ref "Q12") (pin "2") (pinfunction "E_2") (pintype "passive"))
      (node (ref "R43") (pin "1") (pinfunction "1_1") (pintype "passive"))
      (node (ref "R44") (pin "1") (pinfunction "1_1") (pintype "passive"))
      (node (ref "R45") (pin "1") (pinfunction "1_1") (pintype "passive"))
      (node (ref "R47_OR_42") (pin "1") (pinfunction "1_1") (pintype "passive"))
      (node (ref "R5") (pin "1") (pinfunction "1_1") (pintype "passive"))
      (node (ref "R61") (pin "2") (pinfunction "2_2") (pintype "passive"))
      (node (ref "R62") (pin "1") (pinfunction "1_1") (pintype "passive"))
      (node (ref "R63") (pin "1") (pinfunction "1_1") (pintype "passive"))
      (node (ref "R66") (pin "1") (pinfunction "1_1") (pintype "passive"))
      (node (ref "R71") (pin "1") (pinfunction "1_1") (pintype "passive"))
      (node (ref "R81") (pin "1") (pinfunction "1_1") (pintype "passive"))
      (node (ref "U$1") (pin "6") (pinfunction "GND_6") (pintype "power_in"))
      (node (ref "U$2") (pin "6") (pinfunction "GND_6") (pintype "power_in"))
      (node (ref "U$3") (pin "6") (pinfunction "GND_6") (pintype "power_in"))
      (node (ref "U$4") (pin "P$9") (pinfunction "P0.29_P$9") (pintype "bidirectional"))
      (node (ref "U$5") (pin "24") (pinfunction "24_24") (pintype "bidirectional"))
      (node (ref "U$5") (pin "3") (pinfunction "3_3") (pintype "bidirectional"))
      (node (ref "U$5") (pin "30") (pinfunction "30_30") (pintype "bidirectional"))
      (node (ref "U$5") (pin "34") (pinfunction "34_34") (pintype "bidirectional"))
      (node (ref "U$5") (pin "8") (pinfunction "8_8") (pintype "bidirectional"))
      (node (ref "U8") (pin "3") (pinfunction "VIN_3") (pintype "passive"))
    )
    (net (code "4") (name "/GND_INDUCTED") (class "Default")
      (node (ref "L14") (pin "2") (pinfunction "2_2") (pintype "passive"))
      (node (ref "U7") (pin "3") (pinfunction "VIN_3") (pintype "passive"))
    )
    (net (code "5") (name "/HEAD_IN_A") (class "Default")
      (node (ref "R43") (pin "2") (pinfunction "2_2") (pintype "passive"))
      (node (ref "U$3") (pin "1") (pinfunction "IN_A_1") (pintype "input"))
      (node (ref "U$4") (pin "P$3") (pinfunction "P0.23_P$3") (pintype "bidirectional"))
    )
    (net (code "6") (name "/HEAD_IN_B") (class "Default")
      (node (ref "R45") (pin "2") (pinfunction "2_2") (pintype "passive"))
      (node (ref "U$3") (pin "3") (pinfunction "IN_B_3") (pintype "input"))
      (node (ref "U$4") (pin "P$4") (pinfunction "P0.24_P$4") (pintype "bidirectional"))
    )
    (net (code "7") (name "/HEAD_OUT_A") (class "Default")
      (node (ref "JP5") (pin "2") (pinfunction "2_2") (pintype "passive"))
      (node (ref "U$3") (pin "7") (pinfunction "OUT_A_7") (pintype "output"))
    )
    (net (code "8") (name "/HEAD_OUT_B") (class "Default")
      (node (ref "JP5") (pin "1") (pinfunction "1_1") (pintype "passive"))
      (node (ref "U$3") (pin "5") (pinfunction "OUT_B_5") (pintype "output"))
    )
    (net (code "9") (name "/HED_DET") (class "Default")
      (node (ref "JP1") (pin "1") (pinfunction "1_1") (pintype "passive"))
    )
    (net (code "10") (name "/HE_5V") (class "Default")
      (node (ref "JP13") (pin "5") (pinfunction "5_5") (pintype "passive"))
      (node (ref "Q6") (pin "3") (pinfunction "C_3") (pintype "passive"))
    )
    (net (code "11") (name "/H_DET") (class "Default")
      (node (ref "JP13") (pin "1") (pinfunction "1_1") (pintype "passive"))
      (node (ref "U$5") (pin "13") (pinfunction "13_13") (pintype "bidirectional"))
    )
    (net (code "12") (name "/H_L") (class "Default")
      (node (ref "JP10") (pin "2") (pinfunction "2_2") (pintype "passive"))
      (node (ref "R52") (pin "1") (pinfunction "1_1") (pintype "passive"))
    )
    (net (code "13") (name "/H_MID") (class "Default")
      (node (ref "JP10") (pin "3") (pinfunction "3_3") (pintype "passive"))
      (node (ref "R49") (pin "1") (pinfunction "1_1") (pintype "passive"))
    )
    (net (code "14") (name "/H_R") (class "Default")
      (node (ref "JP10") (pin "1") (pinfunction "1_1") (pintype "passive"))
      (node (ref "R51") (pin "1") (pinfunction "1_1") (pintype "passive"))
    )
    (net (code "15") (name "/LED_B") (class "Default")
      (node (ref "JP13") (pin "2") (pinfunction "2_2") (pintype "passive"))
      (node (ref "U$5") (pin "12") (pinfunction "12_12") (pintype "bidirectional"))
    )
    (net (code "16") (name "/LED_G") (class "Default")
      (node (ref "JP13") (pin "3") (pinfunction "3_3") (pintype "passive"))
      (node (ref "U$5") (pin "11") (pinfunction "11_11") (pintype "bidirectional"))
    )
    (net (code "17") (name "/LED_R") (class "Default")
      (node (ref "JP13") (pin "4") (pinfunction "4_4") (pintype "passive"))
      (node (ref "U$5") (pin "10") (pinfunction "10_10") (pintype "bidirectional"))
    )
    (net (code "18") (name "/LEFT_IN_A") (class "Default")
      (node (ref "R44") (pin "2") (pinfunction "2_2") (pintype "passive"))
      (node (ref "U$1") (pin "1") (pinfunction "IN_A_1") (pintype "input"))
      (node (ref "U$4") (pin "P$5") (pinfunction "P0.25_P$5") (pintype "bidirectional"))
    )
    (net (code "19") (name "/LEFT_IN_B") (class "Default")
      (node (ref "R47_OR_42") (pin "2") (pinfunction "2_2") (pintype "passive"))
      (node (ref "U$1") (pin "3") (pinfunction "IN_B_3") (pintype "input"))
      (node (ref "U$4") (pin "P$10") (pinfunction "P0.30_P$10") (pintype "bidirectional"))
    )
    (net (code "20") (name "/LEFT_OUT_A") (class "Default")
      (node (ref "JP3") (pin "2") (pinfunction "2_2") (pintype "passive"))
      (node (ref "U$1") (pin "7") (pinfunction "OUT_A_7") (pintype "output"))
    )
    (net (code "21") (name "/LEFT_OUT_B") (class "Default")
      (node (ref "JP3") (pin "1") (pinfunction "1_1") (pintype "passive"))
      (node (ref "U$1") (pin "5") (pinfunction "OUT_B_5") (pintype "output"))
    )
    (net (code "22") (name "/L_ID") (class "Default")
      (node (ref "JP8") (pin "1") (pinfunction "1_1") (pintype "passive"))
      (node (ref "R18") (pin "1") (pinfunction "1_1") (pintype "passive"))
      (node (ref "R22") (pin "1") (pinfunction "1_1") (pintype "passive"))
    )
    (net (code "23") (name "/L_LED") (class "Default")
      (node (ref "JP8") (pin "3") (pinfunction "3_3") (pintype "passive"))
      (node (ref "R6") (pin "1") (pinfunction "1_1") (pintype "passive"))
    )
    (net (code "24") (name "/OFF") (class "Default")
      (node (ref "JP9") (pin "1") (pinfunction "1_1") (pintype "passive"))
      (node (ref "R81") (pin "2") (pinfunction "2_2") (pintype "passive"))
    )
    (net (code "25") (name "/P0.14") (class "Default")
      (node (ref "R68") (pin "2") (pinfunction "2_2") (pintype "passive"))
      (node (ref "R71") (pin "2") (pinfunction "2_2") (pintype "passive"))
      (node (ref "U$4") (pin "P$25") (pinfunction "P0.14_P$25") (pintype "bidirectional"))
    )
    (net (code "26") (name "/P0.15") (class "Default")
      (node (ref "U$4") (pin "P$26") (pinfunction "P0.15_P$26") (pintype "bidirectional"))
      (node (ref "U$5") (pin "18") (pinfunction "18_18") (pintype "bidirectional"))
    )
    (net (code "27") (name "/P0.17") (class "Default")
      (node (ref "U$4") (pin "P$28") (pinfunction "P0.17_P$28") (pintype "bidirectional"))
      (node (ref "U$5") (pin "20") (pinfunction "20_20") (pintype "bidirectional"))
    )
    (net (code "28") (name "/P0.18") (class "Default")
      (node (ref "U$4") (pin "P$29") (pinfunction "P0.18_P$29") (pintype "bidirectional"))
      (node (ref "U$5") (pin "21") (pinfunction "21_21") (pintype "bidirectional"))
    )
    (net (code "29") (name "/P0.19") (class "Default")
      (node (ref "U$4") (pin "P$30") (pinfunction "P0.19_P$30") (pintype "bidirectional"))
      (node (ref "U$5") (pin "22") (pinfunction "22_22") (pintype "bidirectional"))
    )
    (net (code "30") (name "/PAIR_BTN") (class "Default")
      (node (ref "JP11") (pin "1") (pinfunction "1_1") (pintype "passive"))
      (node (ref "U$4") (pin "P$24") (pinfunction "P0.13_P$24") (pintype "bidirectional"))
    )
    (net (code "31") (name "/PAIR_LED+") (class "Default")
      (node (ref "JP11") (pin "3") (pinfunction "3_3") (pintype "passive"))
      (node (ref "U$4") (pin "P$22") (pinfunction "P0.11_P$22") (pintype "bidirectional"))
    )
    (net (code "32") (name "/PAIR_LED-") (class "Default")
      (node (ref "JP11") (pin "4") (pinfunction "4_4") (pintype "passive"))
      (node (ref "R5") (pin "2") (pinfunction "2_2") (pintype "passive"))
    )
    (net (code "33") (name "/Q6_B") (class "Default")
      (node (ref "Q6") (pin "1") (pinfunction "B_1") (pintype "passive"))
      (node (ref "R27") (pin "1") (pinfunction "1_1") (pintype "passive"))
    )
    (net (code "34") (name "/Q10_B") (class "Default")
      (node (ref "Q10") (pin "1") (pinfunction "B_1") (pintype "passive"))
      (node (ref "R54") (pin "2") (pinfunction "2_2") (pintype "passive"))
      (node (ref "R60") (pin "2") (pinfunction "2_2") (pintype "passive"))
    )
    (net (code "35") (name "/Q10_C") (class "Default")
      (node (ref "Q10") (pin "3") (pinfunction "C_3") (pintype "passive"))
      (node (ref "R59") (pin "2") (pinfunction "2_2") (pintype "passive"))
    )
    (net (code "36") (name "/Q11_B") (class "Default")
      (node (ref "Q11") (pin "1") (pinfunction "B_1") (pintype "passive"))
      (node (ref "R64") (pin "1") (pinfunction "1_1") (pintype "passive"))
    )
    (net (code "37") (name "/Q11_C") (class "Default")
      (node (ref "Q11") (pin "3") (pinfunction "C_3") (pintype "passive"))
      (node (ref "R60") (pin "1") (pinfunction "1_1") (pintype "passive"))
    )
    (net (code "38") (name "/Q12_B") (class "Default")
      (node (ref "Q12") (pin "1") (pinfunction "B_1") (pintype "passive"))
      (node (ref "R68") (pin "1") (pinfunction "1_1") (pintype "passive"))
    )
    (net (code "39") (name "/Q12_C") (class "Default")
      (node (ref "C29") (pin "2") (pinfunction "2_2") (pintype "passive"))
      (node (ref "Q12") (pin "3") (pinfunction "C_3") (pintype "passive"))
      (node (ref "U$5") (pin "5") (pinfunction "5_5") (pintype "bidirectional"))
    )
    (net (code "40") (name "/Q13_B") (class "Default")
      (node (ref "Q13") (pin "1") (pinfunction "B_1") (pintype "passive"))
      (node (ref "R99") (pin "1") (pinfunction "1_1") (pintype "passive"))
    )
    (net (code "41") (name "/Q13_C") (class "Default")
      (node (ref "Q13") (pin "3") (pinfunction "C_3") (pintype "passive"))
      (node (ref "R6") (pin "2") (pinfunction "2_2") (pintype "passive"))
    )
    (net (code "42") (name "/Q14_B") (class "Default")
      (node (ref "Q14") (pin "1") (pinfunction "B_1") (pintype "passive"))
      (node (ref "R100") (pin "1") (pinfunction "1_1") (pintype "passive"))
    )
    (net (code "43") (name "/Q14_C") (class "Default")
      (node (ref "Q14") (pin "3") (pinfunction "C_3") (pintype "passive"))
      (node (ref "R7") (pin "1") (pinfunction "1_1") (pintype "passive"))
    )
    (net (code "44") (name "/R22_B") (class "Default")
      (node (ref "R22") (pin "2") (pinfunction "2_2") (pintype "passive"))
      (node (ref "U$4") (pin "P$12") (pinfunction "P0.1_P$12") (pintype "bidirectional"))
    )
    (net (code "45") (name "/R23_B") (class "Default")
      (node (ref "R18") (pin "2") (pinfunction "2_2") (pintype "passive"))
      (node (ref "R23") (pin "2") (pinfunction "2_2") (pintype "passive"))
      (node (ref "U$4") (pin "P$16") (pinfunction "P0.5_P$16") (pintype "bidirectional"))
    )
    (net (code "46") (name "/R25_B") (class "Default")
      (node (ref "R25") (pin "2") (pinfunction "2_2") (pintype "passive"))
      (node (ref "U$5") (pin "6") (pinfunction "6_6") (pintype "bidirectional"))
    )
    (net (code "47") (name "/R27_B") (class "Default")
      (node (ref "R27") (pin "2") (pinfunction "2_2") (pintype "passive"))
      (node (ref "U$5") (pin "9") (pinfunction "9_9") (pintype "bidirectional"))
    )
    (net (code "48") (name "/R29_B") (class "Default")
      (node (ref "R29") (pin "2") (pinfunction "2_2") (pintype "passive"))
      (node (ref "U$4") (pin "P$15") (pinfunction "P0.4_P$15") (pintype "bidirectional"))
    )
    (net (code "49") (name "/R49_B") (class "Default")
      (node (ref "R49") (pin "2") (pinfunction "2_2") (pintype "passive"))
      (node (ref "U$4") (pin "P$13") (pinfunction "P0.2_P$13") (pintype "bidirectional"))
    )
    (net (code "50") (name "/R51_B") (class "Default")
      (node (ref "R51") (pin "2") (pinfunction "2_2") (pintype "passive"))
      (node (ref "U$4") (pin "P$2") (pinfunction "P0.22_P$2") (pintype "bidirectional"))
    )
    (net (code "51") (name "/R52_B") (class "Default")
      (node (ref "R52") (pin "2") (pinfunction "2_2") (pintype "passive"))
      (node (ref "U$4") (pin "P$18") (pinfunction "P0.7_P$18") (pintype "bidirectional"))
    )
    (net (code "52") (name "/R55_B") (class "Default")
      (node (ref "R55") (pin "2") (pinfunction "2_2") (pintype "passive"))
      (node (ref "U$4") (pin "P$14") (pinfunction "P0.3_P$14") (pintype "bidirectional"))
    )
    (net (code "53") (name "/R61_A") (class "Default")
      (node (ref "C26") (pin "1") (pinfunction "1_1") (pintype "passive"))
      (node (ref "R55") (pin "1") (pinfunction "1_1") (pintype "passive"))
      (node (ref "R59") (pin "1") (pinfunction "1_1") (pintype "passive"))
      (node (ref "R61") (pin "1") (pinfunction "1_1") (pintype "passive"))
    )
    (net (code "54") (name "/R64_B") (class "Default")
      (node (ref "R64") (pin "2") (pinfunction "2_2") (pintype "passive"))
      (node (ref "R66") (pin "2") (pinfunction "2_2") (pintype "passive"))
      (node (ref "U$4") (pin "P$23") (pinfunction "P0.12_P$23") (pintype "bidirectional"))
    )
    (net (code "55") (name "/R76_A") (class "Default")
      (node (ref "C11") (pin "2") (pinfunction "2_2") (pintype "passive"))
      (node (ref "R76") (pin "1") (pinfunction "1_1") (pintype "passive"))
    )
    (net (code "56") (name "/R99_B") (class "Default")
      (node (ref "R99") (pin "2") (pinfunction "2_2") (pintype "passive"))
      (node (ref "U$5") (pin "14") (pinfunction "14_14") (pintype "bidirectional"))
    )
    (net (code "57") (name "/R100_B") (class "Default")
      (node (ref "R100") (pin "2") (pinfunction "2_2") (pintype "passive"))
      (node (ref "U$5") (pin "15") (pinfunction "15_15") (pintype "bidirectional"))
    )
    (net (code "58") (name "/RIGHT_IN_A") (class "Default")
      (node (ref "R62") (pin "2") (pinfunction "2_2") (pintype "passive"))
      (node (ref "U$2") (pin "1") (pinfunction "IN_A_1") (pintype "input"))
      (node (ref "U$4") (pin "P$19") (pinfunction "P0.8_P$19") (pintype "bidirectional"))
    )
    (net (code "59") (name "/RIGHT_IN_B") (class "Default")
      (node (ref "R63") (pin "2") (pinfunction "2_2") (pintype "passive"))
      (node (ref "U$2") (pin "3") (pinfunction "IN_B_3") (pintype "input"))
      (node (ref "U$4") (pin "P$20") (pinfunction "P0.9_P$20") (pintype "bidirectional"))
    )
    (net (code "60") (name "/RIGHT_OUT_A") (class "Default")
      (node (ref "JP4") (pin "2") (pinfunction "2_2") (pintype "passive"))
      (node (ref "U$2") (pin "7") (pinfunction "OUT_A_7") (pintype "output"))
    )
    (net (code "61") (name "/RIGHT_OUT_B") (class "Default")
      (node (ref "JP4") (pin "1") (pinfunction "1_1") (pintype "passive"))
      (node (ref "U$2") (pin "5") (pinfunction "OUT_B_5") (pintype "output"))
    )
    (net (code "62") (name "/R_ID") (class "Default")
      (node (ref "JP7") (pin "1") (pinfunction "1_1") (pintype "passive"))
      (node (ref "R23") (pin "1") (pinfunction "1_1") (pintype "passive"))
      (node (ref "R29") (pin "1") (pinfunction "1_1") (pintype "passive"))
    )
    (net (code "63") (name "/R_LED") (class "Default")
      (node (ref "JP7") (pin "3") (pinfunction "3_3") (pintype "passive"))
      (node (ref "R7") (pin "2") (pinfunction "2_2") (pintype "passive"))
    )
    (net (code "64") (name "/SCK") (class "Default")
      (node (ref "JP14") (pin "4") (pinfunction "4_4") (pintype "passive"))
      (node (ref "JP15") (pin "2") (pinfunction "2_2") (pintype "passive"))
      (node (ref "U$5") (pin "26") (pinfunction "26_26") (pintype "bidirectional"))
    )
    (net (code "65") (name "/SCL") (class "Default")
      (node (ref "U$5") (pin "17") (pinfunction "17_17") (pintype "bidirectional"))
    )
    (net (code "66") (name "/SDA") (class "Default")
      (node (ref "JP14") (pin "3") (pinfunction "3_3") (pintype "passive"))
      (node (ref "U$5") (pin "16") (pinfunction "16_16") (pintype "bidirectional"))
    )
    (net (code "67") (name "/SI") (class "Default")
      (node (ref "JP15") (pin "5") (pinfunction "5_5") (pintype "passive"))
      (node (ref "U$5") (pin "28") (pinfunction "28_28") (pintype "bidirectional"))
    )
    (net (code "68") (name "/SICS") (class "Default")
      (node (ref "U$5") (pin "25") (pinfunction "25_25") (pintype "bidirectional"))
    )
    (net (code "69") (name "/SO") (class "Default")
      (node (ref "JP15") (pin "4") (pinfunction "4_4") (pintype "passive"))
      (node (ref "U$5") (pin "27") (pinfunction "27_27") (pintype "bidirectional"))
    )
    (net (code "70") (name "/SP+") (class "Default")
      (node (ref "L12") (pin "2") (pinfunction "2_2") (pintype "passive"))
      (node (ref "U$5") (pin "31") (pinfunction "31_31") (pintype "bidirectional"))
    )
    (net (code "71") (name "/SP+_OUT") (class "Default")
      (node (ref "C38") (pin "2") (pinfunction "2_2") (pintype "passive"))
      (node (ref "JP6") (pin "1") (pinfunction "1_1") (pintype "passive"))
      (node (ref "L12") (pin "1") (pinfunction "1_1") (pintype "passive"))
    )
    (net (code "72") (name "/SP-") (class "Default")
      (node (ref "L11") (pin "2") (pinfunction "2_2") (pintype "passive"))
      (node (ref "U$5") (pin "33") (pinfunction "33_33") (pintype "bidirectional"))
    )
    (net (code "73") (name "/SP-_OUT") (class "Default")
      (node (ref "C39") (pin "2") (pinfunction "2_2") (pintype "passive"))
      (node (ref "JP6") (pin "2") (pinfunction "2_2") (pintype "passive"))
      (node (ref "L11") (pin "1") (pinfunction "1_1") (pintype "passive"))
    )
    (net (code "74") (name "/SWCLK") (class "Default")
      (node (ref "JP12") (pin "2") (pinfunction "2_2") (pintype "passive"))
      (node (ref "U$4") (pin "P$27") (pinfunction "P0.16_P$27") (pintype "bidirectional"))
      (node (ref "U$5") (pin "19") (pinfunction "19_19") (pintype "bidirectional"))
    )
    (net (code "75") (name "/SWDIO") (class "Default")
      (node (ref "D14") (pin "A") (pinfunction "A_A") (pintype "passive"))
      (node (ref "JP12") (pin "3") (pinfunction "3_3") (pintype "passive"))
      (node (ref "U$4") (pin "P$31") (pinfunction "P0.20_P$31") (pintype "bidirectional"))
    )
    (net (code "76") (name "/U7_VIN") (class "Default")
      (node (ref "C34") (pin "2") (pinfunction "2_2") (pintype "passive"))
      (node (ref "L13") (pin "2") (pinfunction "2_2") (pintype "passive"))
      (node (ref "Q10") (pin "2") (pinfunction "E_2") (pintype "passive"))
      (node (ref "R54") (pin "1") (pinfunction "1_1") (pintype "passive"))
      (node (ref "U7") (pin "1") (pinfunction "VSS_1") (pintype "passive"))
    )
    (net (code "77") (name "/U8_VIN") (class "Default")
      (node (ref "C35") (pin "2") (pinfunction "2_2") (pintype "passive"))
      (node (ref "L9") (pin "1") (pinfunction "1_1") (pintype "passive"))
      (node (ref "U8") (pin "1") (pinfunction "VSS_1") (pintype "passive"))
    )
    (net (code "78") (name "/U8_VOUT") (class "Default")
      (node (ref "C24") (pin "2") (pinfunction "2_2") (pintype "passive"))
      (node (ref "C25") (pin "2") (pinfunction "2_2") (pintype "passive"))
      (node (ref "C36") (pin "2") (pinfunction "2_2") (pintype "passive"))
      (node (ref "R25") (pin "1") (pinfunction "1_1") (pintype "passive"))
      (node (ref "R77") (pin "1") (pinfunction "1_1") (pintype "passive"))
      (node (ref "R77") (pin "2") (pinfunction "2_2") (pintype "passive"))
      (node (ref "U8") (pin "2") (pinfunction "VOUT_2") (pintype "passive"))
      (node (ref "U8") (pin "2@1") (pinfunction "VOUT_2@1") (pintype "passive"))
    )
    (net (code "79") (name "/VCC_3") (class "Default")
      (node (ref "JP1") (pin "2") (pinfunction "2_2") (pintype "passive"))
      (node (ref "JP10") (pin "4") (pinfunction "4_4") (pintype "passive"))
      (node (ref "U$4") (pin "P$11") (pinfunction "P0.00_P$11") (pintype "bidirectional"))
    )
    (net (code "80") (name "/VCC_33") (class "Default")
      (node (ref "C20A") (pin "2") (pinfunction "2_2") (pintype "passive"))
      (node (ref "C21") (pin "2") (pinfunction "2_2") (pintype "passive"))
      (node (ref "C22A") (pin "2") (pinfunction "2_2") (pintype "passive"))
      (node (ref "C23") (pin "2") (pinfunction "2_2") (pintype "passive"))
      (node (ref "C31") (pin "2") (pinfunction "2_2") (pintype "passive"))
      (node (ref "C33") (pin "2") (pinfunction "2_2") (pintype "passive"))
      (node (ref "JP12") (pin "4") (pinfunction "4_4") (pintype "passive"))
      (node (ref "JP14") (pin "5") (pinfunction "5_5") (pintype "passive"))
      (node (ref "JP15") (pin "1") (pinfunction "1_1") (pintype "passive"))
      (node (ref "L9") (pin "2") (pinfunction "2_2") (pintype "passive"))
      (node (ref "Q13") (pin "2") (pinfunction "E_2") (pintype "passive"))
      (node (ref "Q14") (pin "2") (pinfunction "E_2") (pintype "passive"))
      (node (ref "Q6") (pin "2") (pinfunction "E_2") (pintype "passive"))
      (node (ref "R26") (pin "1") (pinfunction "1_1") (pintype "passive"))
      (node (ref "R26") (pin "2") (pinfunction "2_2") (pintype "passive"))
      (node (ref "R30") (pin "1") (pinfunction "1_1") (pintype "passive"))
      (node (ref "R30") (pin "2") (pinfunction "2_2") (pintype "passive"))
      (node (ref "R76") (pin "2") (pinfunction "2_2") (pintype "passive"))
      (node (ref "U$4") (pin "P$8") (pinfunction "P0.28_P$8") (pintype "bidirectional"))
      (node (ref "U$5") (pin "2") (pinfunction "2_2") (pintype "bidirectional"))
      (node (ref "U$5") (pin "23") (pinfunction "23_23") (pintype "bidirectional"))
      (node (ref "U$5") (pin "32") (pinfunction "32_32") (pintype "bidirectional"))
      (node (ref "U$5") (pin "4") (pinfunction "4_4") (pintype "bidirectional"))
      (node (ref "U$5") (pin "7") (pinfunction "7_7") (pintype "bidirectional"))
      (node (ref "U7") (pin "2") (pinfunction "VOUT_2") (pintype "passive"))
      (node (ref "U7") (pin "2@1") (pinfunction "VOUT_2@1") (pintype "passive"))
    )
    (net (code "81") (name "/VCC_ON") (class "Default")
      (node (ref "C37") (pin "+") (pinfunction "+_+") (pintype "passive"))
      (node (ref "D14") (pin "C") (pinfunction "C_C") (pintype "passive"))
      (node (ref "JP9") (pin "2") (pinfunction "2_2") (pintype "passive"))
      (node (ref "L13") (pin "1") (pinfunction "1_1") (pintype "passive"))
    )
    (net (code "82") (name "/VCV_M") (class "Default")
      (node (ref "C16") (pin "2") (pinfunction "2_2") (pintype "passive"))
      (node (ref "C17") (pin "2") (pinfunction "2_2") (pintype "passive"))
      (node (ref "C18") (pin "2") (pinfunction "2_2") (pintype "passive"))
      (node (ref "C19") (pin "2") (pinfunction "2_2") (pintype "passive"))
      (node (ref "C27") (pin "2") (pinfunction "2_2") (pintype "passive"))
      (node (ref "C28") (pin "2") (pinfunction "2_2") (pintype "passive"))
      (node (ref "F1") (pin "P$1") (pinfunction "1_P$1") (pintype "passive"))
      (node (ref "JP9") (pin "3") (pinfunction "3_3") (pintype "passive"))
      (node (ref "U$1") (pin "4") (pinfunction "VCC_4") (pintype "power_in"))
      (node (ref "U$2") (pin "4") (pinfunction "VCC_4") (pintype "power_in"))
      (node (ref "U$3") (pin "4") (pinfunction "VCC_4") (pintype "power_in"))
    )
    (net (code "83") (name "/VPP") (class "Default")
      (node (ref "JP14") (pin "1") (pinfunction "1_1") (pintype "passive"))
      (node (ref "U$5") (pin "1") (pinfunction "1_1") (pintype "bidirectional"))
    )
    (net (code "84") (name "unconnected-(U$1-NC-Pad2)") (class "Default")
      (node (ref "U$1") (pin "2") (pinfunction "NC_2") (pintype "no_connect"))
    )
    (net (code "85") (name "unconnected-(U$1-NC-Pad8)") (class "Default")
      (node (ref "U$1") (pin "8") (pinfunction "NC_8") (pintype "no_connect"))
    )
    (net (code "86") (name "unconnected-(U$2-NC-Pad2)") (class "Default")
      (node (ref "U$2") (pin "2") (pinfunction "NC_2") (pintype "no_connect"))
    )
    (net (code "87") (name "unconnected-(U$2-NC-Pad8)") (class "Default")
      (node (ref "U$2") (pin "8") (pinfunction "NC_8") (pintype "no_connect"))
    )
    (net (code "88") (name "unconnected-(U$3-NC-Pad2)") (class "Default")
      (node (ref "U$3") (pin "2") (pinfunction "NC_2") (pintype "no_connect"))
    )
    (net (code "89") (name "unconnected-(U$3-NC-Pad8)") (class "Default")
      (node (ref "U$3") (pin "8") (pinfunction "NC_8") (pintype "no_connect"))
    )
    (net (code "90") (name "unconnected-(U$4-P0.6-PadP$17)") (class "Default")
      (node (ref "U$4") (pin "P$17") (pinfunction "P0.6_P$17") (pintype "bidirectional"))
    )
    (net (code "91") (name "unconnected-(U$4-P0.10-PadP$21)") (class "Default")
      (node (ref "U$4") (pin "P$21") (pinfunction "P0.10_P$21") (pintype "bidirectional"))
    )
    (net (code "92") (name "unconnected-(U$4-P0.21-PadP$1)") (class "Default")
      (node (ref "U$4") (pin "P$1") (pinfunction "P0.21_P$1") (pintype "bidirectional"))
    )
    (net (code "93") (name "unconnected-(U$4-P0.26-PadP$6)") (class "Default")
      (node (ref "U$4") (pin "P$6") (pinfunction "P0.26_P$6") (pintype "bidirectional"))
    )
    (net (code "94") (name "unconnected-(U$4-P0.27-PadP$7)") (class "Default")
      (node (ref "U$4") (pin "P$7") (pinfunction "P0.27_P$7") (pintype "bidirectional"))
    )
  )
)
